# reader.net
KiCad netlist of a schematic drawn in EAGLE
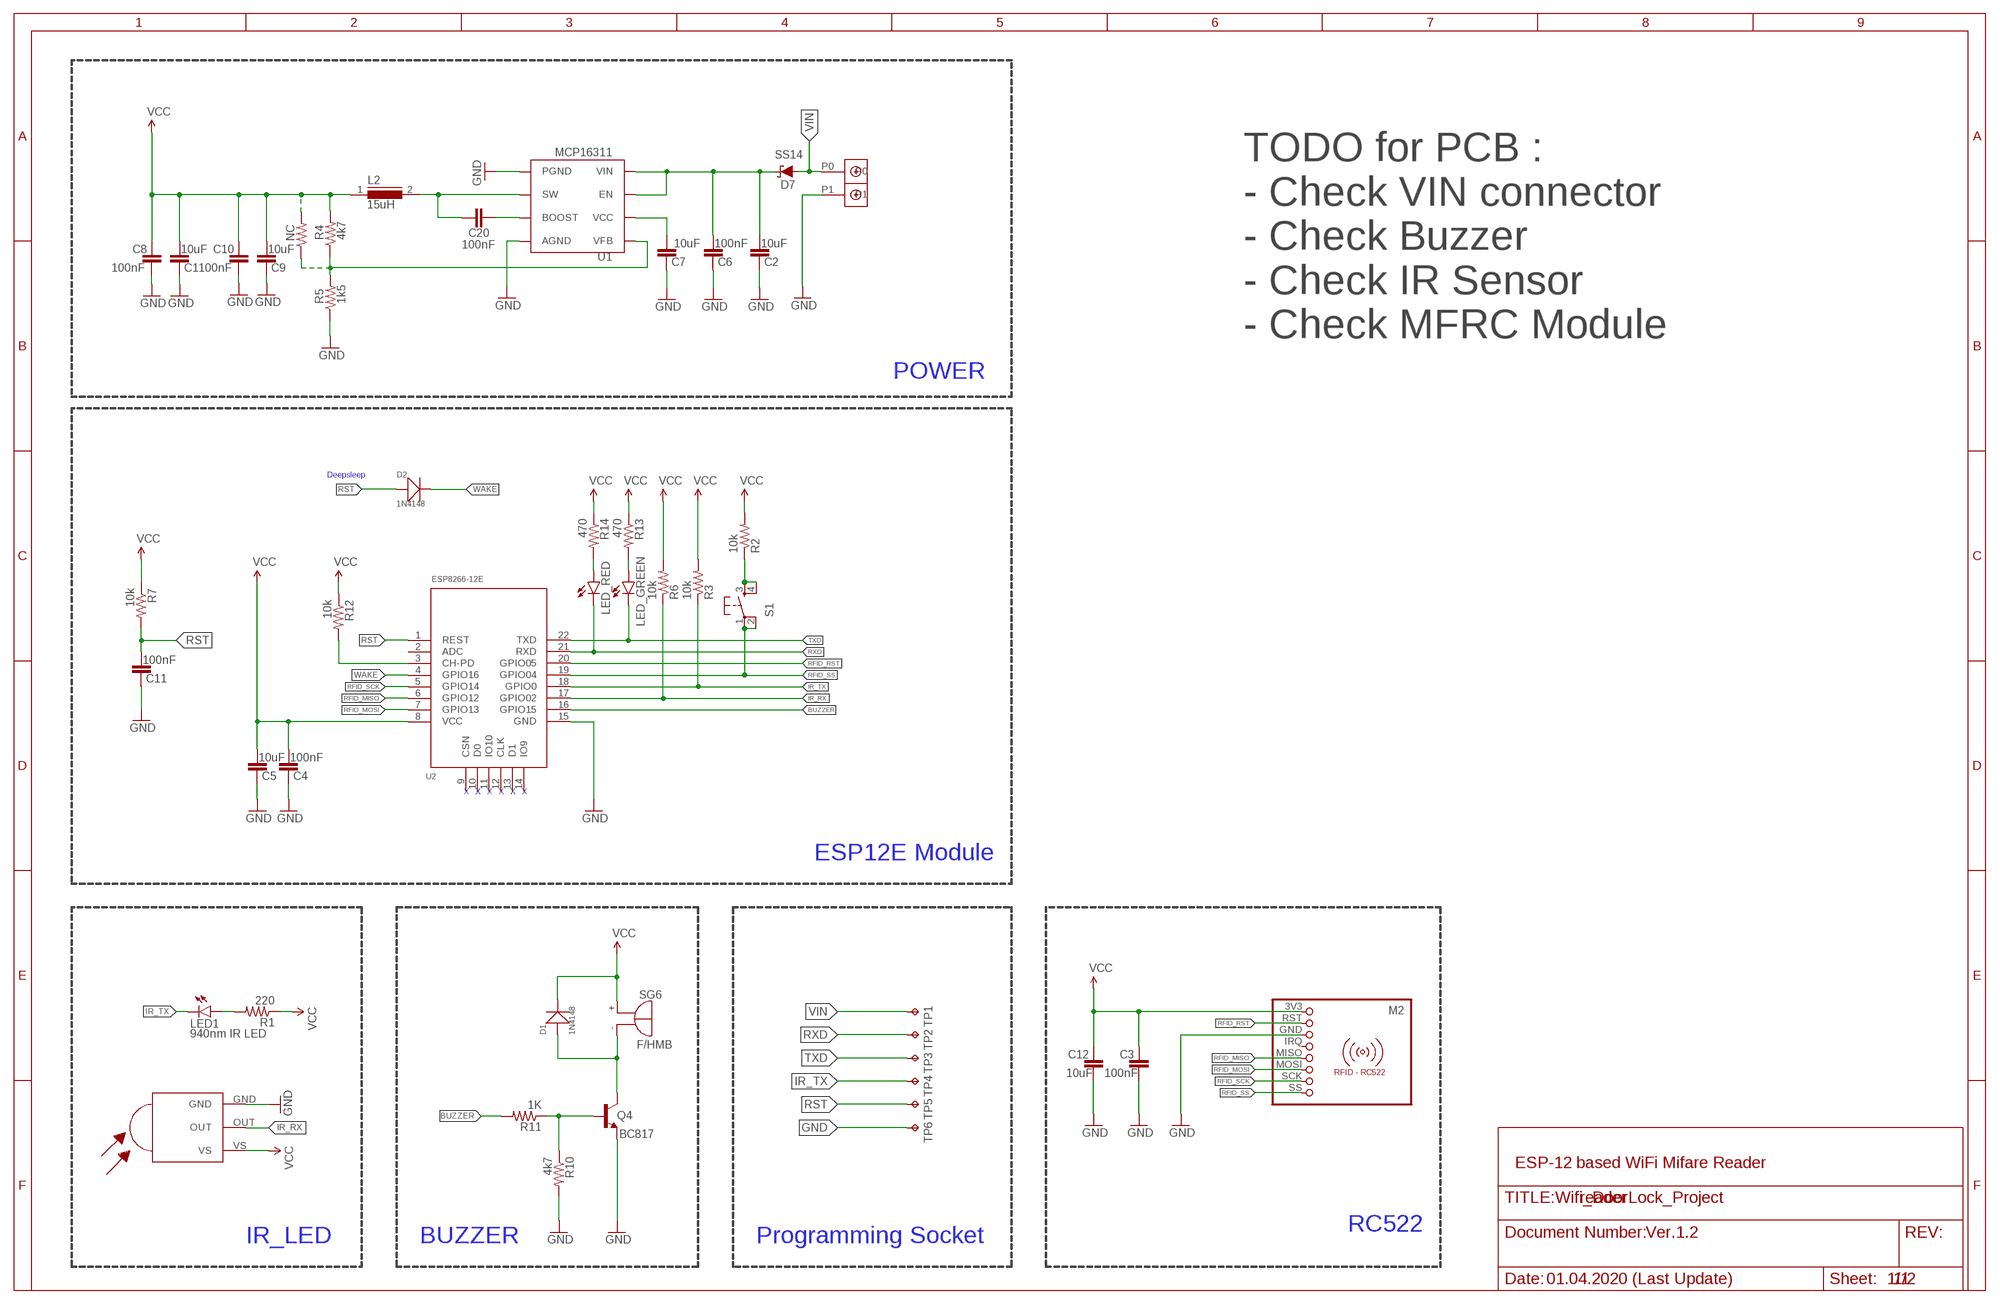
[diagram p0: schematic, sheet 1]

(export (version "E")
  (design (tool "Eeschema 10.0.6"))
  (components
    (comp (ref "C1")
      (value "10uF")
      (footprint "eagle-import:C0805")
      (libsource (lib "eagle-import") (part "C-EUC0805"))
    )
    (comp (ref "C2")
      (value "10uF")
      (footprint "eagle-import:C0805")
      (libsource (lib "eagle-import") (part "C-EUC0805"))
    )
    (comp (ref "C3")
      (value "100nF")
      (footprint "eagle-import:C0805")
      (libsource (lib "eagle-import") (part "C-EUC0805"))
    )
    (comp (ref "C4")
      (value "100nF")
      (footprint "eagle-import:C0805")
      (libsource (lib "eagle-import") (part "C-EUC0805"))
    )
    (comp (ref "C5")
      (value "10uF")
      (footprint "eagle-import:C0805")
      (libsource (lib "eagle-import") (part "C-EUC0805"))
    )
    (comp (ref "C6")
      (value "100nF")
      (footprint "eagle-import:C0805")
      (libsource (lib "eagle-import") (part "C-EUC0805"))
    )
    (comp (ref "C7")
      (value "10uF")
      (footprint "eagle-import:C0805")
      (libsource (lib "eagle-import") (part "C-EUC0805"))
    )
    (comp (ref "C8")
      (value "100nF")
      (footprint "eagle-import:C0805")
      (libsource (lib "eagle-import") (part "C-EUC0805"))
    )
    (comp (ref "C9")
      (value "10uF")
      (footprint "eagle-import:C0805")
      (libsource (lib "eagle-import") (part "C-EUC0805"))
    )
    (comp (ref "C10")
      (value "100nF")
      (footprint "eagle-import:C0805")
      (libsource (lib "eagle-import") (part "C-EUC0805"))
    )
    (comp (ref "C11")
      (value "100nF")
      (footprint "eagle-import:C0805")
      (libsource (lib "eagle-import") (part "C-EUC0805"))
    )
    (comp (ref "C12")
      (value "10uF")
      (footprint "eagle-import:C0805")
      (libsource (lib "eagle-import") (part "C-EUC0805"))
    )
    (comp (ref "C20")
      (value "100nF")
      (footprint "eagle-import:C0805")
      (libsource (lib "eagle-import") (part "C-EUC0805"))
    )
    (comp (ref "D1")
      (value "1N4148")
      (footprint "eagle-import:LL-34")
      (libsource (lib "eagle-import") (part "SMD-DIODE-SWITCH-1N4148(LL-34)"))
    )
    (comp (ref "D2")
      (value "1N4148")
      (footprint "eagle-import:LL-34")
      (libsource (lib "eagle-import") (part "SMD-DIODE-SWITCH-1N4148(LL-34)"))
    )
    (comp (ref "D7")
      (value "SS14")
      (footprint "eagle-import:SMA-DIODE")
      (libsource (lib "eagle-import") (part "DIODE-SCHOTTKY-SS14"))
    )
    (comp (ref "L2")
      (value "15uH")
      (footprint "eagle-import:DR74")
      (libsource (lib "eagle-import") (part "DR74"))
    )
    (comp (ref "LED1")
      (value "940nm IR LED")
      (footprint "eagle-import:LED3MM")
      (libsource (lib "eagle-import") (part "LED3MM"))
    )
    (comp (ref "LED_GREEN")
      (value "LED3MM")
      (footprint "eagle-import:LED3MM")
      (libsource (lib "eagle-import") (part "LED3MM"))
    )
    (comp (ref "LED_RED")
      (value "LED3MM")
      (footprint "eagle-import:LED3MM")
      (libsource (lib "eagle-import") (part "LED3MM"))
    )
    (comp (ref "M2")
      (value "RFID-RC522")
      (footprint "eagle-import:RFID-RC522")
      (libsource (lib "eagle-import") (part "RFID-RC522"))
    )
    (comp (ref "NC")
      (value "R-US_M0805")
      (footprint "eagle-import:M0805")
      (libsource (lib "eagle-import") (part "R-US_M0805"))
    )
    (comp (ref "Q4")
      (value "BC817")
      (footprint "eagle-import:SOT-23")
      (libsource (lib "eagle-import") (part "TRANSISTOR_BJT_NPN-SOT-23-BCE"))
    )
    (comp (ref "R1")
      (value "220")
      (footprint "eagle-import:M0805")
      (libsource (lib "eagle-import") (part "R-US_M0805"))
    )
    (comp (ref "R2")
      (value "10k")
      (footprint "eagle-import:M0805")
      (libsource (lib "eagle-import") (part "R-US_M0805"))
    )
    (comp (ref "R3")
      (value "10k")
      (footprint "eagle-import:M0805")
      (libsource (lib "eagle-import") (part "R-US_M0805"))
    )
    (comp (ref "R4")
      (value "4k7")
      (footprint "eagle-import:M0805")
      (libsource (lib "eagle-import") (part "R-US_M0805"))
    )
    (comp (ref "R5")
      (value "1k5")
      (footprint "eagle-import:M0805")
      (libsource (lib "eagle-import") (part "R-US_M0805"))
    )
    (comp (ref "R6")
      (value "10k")
      (footprint "eagle-import:M0805")
      (libsource (lib "eagle-import") (part "R-US_M0805"))
    )
    (comp (ref "R7")
      (value "10k")
      (footprint "eagle-import:M0805")
      (libsource (lib "eagle-import") (part "R-US_M0805"))
    )
    (comp (ref "R10")
      (value "4k7")
      (footprint "eagle-import:M0805")
      (libsource (lib "eagle-import") (part "R-US_M0805"))
    )
    (comp (ref "R11")
      (value "1K")
      (footprint "eagle-import:M0805")
      (libsource (lib "eagle-import") (part "R-US_M0805"))
    )
    (comp (ref "R12")
      (value "10k")
      (footprint "eagle-import:M0805")
      (libsource (lib "eagle-import") (part "R-US_M0805"))
    )
    (comp (ref "R13")
      (value "470")
      (footprint "eagle-import:M0805")
      (libsource (lib "eagle-import") (part "R-US_M0805"))
    )
    (comp (ref "R14")
      (value "470")
      (footprint "eagle-import:M0805")
      (libsource (lib "eagle-import") (part "R-US_M0805"))
    )
    (comp (ref "S1")
      (value "FLASH")
      (footprint "eagle-import:TACTILE-PTH")
      (libsource (lib "eagle-import") (part "TAC_SWITCHPTH"))
    )
    (comp (ref "SG6")
      (value "F/HMB")
      (footprint "eagle-import:F_HMB")
      (libsource (lib "eagle-import") (part "F/HMB"))
    )
    (comp (ref "TP1")
      (value "TPTP20SQ")
      (footprint "eagle-import:TP20SQ")
      (libsource (lib "eagle-import") (part "TPTP20SQ"))
    )
    (comp (ref "TP2")
      (value "TPTP20SQ")
      (footprint "eagle-import:TP20SQ")
      (libsource (lib "eagle-import") (part "TPTP20SQ"))
    )
    (comp (ref "TP3")
      (value "TPTP20SQ")
      (footprint "eagle-import:TP20SQ")
      (libsource (lib "eagle-import") (part "TPTP20SQ"))
    )
    (comp (ref "TP4")
      (value "TPTP20SQ")
      (footprint "eagle-import:TP20SQ")
      (libsource (lib "eagle-import") (part "TPTP20SQ"))
    )
    (comp (ref "TP5")
      (value "TPTP20SQ")
      (footprint "eagle-import:TP20SQ")
      (libsource (lib "eagle-import") (part "TPTP20SQ"))
    )
    (comp (ref "TP6")
      (value "TPTP20SQ")
      (footprint "eagle-import:TP20SQ")
      (libsource (lib "eagle-import") (part "TPTP20SQ"))
    )
    (comp (ref "U$1")
      (value "DBCONN-1X2")
      (footprint "eagle-import:DBCONN-1X2")
      (libsource (lib "eagle-import") (part "DBCONN-1X2"))
    )
    (comp (ref "U$3")
      (value "TSOP18")
      (footprint "eagle-import:TSOP-382")
      (fields
        (field (name "DIGI-KEY_PART_NUMBER") "751-1227-ND")
        (field (name "MF") "Vishay")
        (field (name "MP") "TSOP38238")
      )
      (libsource (lib "eagle-import") (part "TSOP38238"))
    )
    (comp (ref "U1")
      (value "MCP16311")
      (footprint "eagle-import:MSOP8")
      (libsource (lib "eagle-import") (part "MCP16311"))
    )
    (comp (ref "U2")
      (value "ESP8266-12E")
      (footprint "eagle-import:LGA22-2.0-24X16MM")
      (fields (field (name "MPN") "ESP8266-12E/ESP-12E"))
      (libsource (lib "eagle-import") (part "MOUDLE-WIFI-ESP8266-12E/ESP-12E(22P-24X16MM)"))
    )
  )
  (nets
    (net (code "1") (name "BUZZER") (class "Default")
      (node (ref "R11") (pin "2") (pinfunction "2_2") (pintype "passive"))
      (node (ref "U2") (pin "16") (pinfunction "GPIO15_16") (pintype "bidirectional"))
    )
    (net (code "2") (name "GND") (class "Default")
      (node (ref "C1") (pin "1") (pinfunction "1_1") (pintype "passive"))
      (node (ref "C10") (pin "2") (pinfunction "2_2") (pintype "passive"))
      (node (ref "C11") (pin "1") (pinfunction "1_1") (pintype "passive"))
      (node (ref "C12") (pin "2") (pinfunction "2_2") (pintype "passive"))
      (node (ref "C2") (pin "1") (pinfunction "1_1") (pintype "passive"))
      (node (ref "C3") (pin "2") (pinfunction "2_2") (pintype "passive"))
      (node (ref "C4") (pin "1") (pinfunction "1_1") (pintype "passive"))
      (node (ref "C5") (pin "1") (pinfunction "1_1") (pintype "passive"))
      (node (ref "C6") (pin "1") (pinfunction "1_1") (pintype "passive"))
      (node (ref "C7") (pin "1") (pinfunction "1_1") (pintype "passive"))
      (node (ref "C8") (pin "2") (pinfunction "2_2") (pintype "passive"))
      (node (ref "C9") (pin "1") (pinfunction "1_1") (pintype "passive"))
      (node (ref "M2") (pin "GND") (pinfunction "3_GND") (pintype "passive"))
      (node (ref "Q4") (pin "3") (pinfunction "E_3") (pintype "passive"))
      (node (ref "R10") (pin "2") (pinfunction "2_2") (pintype "passive"))
      (node (ref "R5") (pin "1") (pinfunction "1_1") (pintype "passive"))
      (node (ref "TP6") (pin "TP") (pinfunction "TP_TP") (pintype "input"))
      (node (ref "U$1") (pin "P1") (pinfunction "P1_P1") (pintype "bidirectional"))
      (node (ref "U$3") (pin "GND") (pinfunction "GND_GND") (pintype "bidirectional"))
      (node (ref "U1") (pin "AGND") (pinfunction "AGND_AGND") (pintype "bidirectional"))
      (node (ref "U1") (pin "PGND") (pinfunction "PGND_PGND") (pintype "bidirectional"))
      (node (ref "U2") (pin "15") (pinfunction "GND_15") (pintype "bidirectional"))
    )
    (net (code "3") (name "IR_RX") (class "Default")
      (node (ref "R6") (pin "1") (pinfunction "1_1") (pintype "passive"))
      (node (ref "U$3") (pin "OUT") (pinfunction "OUT_OUT") (pintype "bidirectional"))
      (node (ref "U2") (pin "17") (pinfunction "GPIO02_17") (pintype "bidirectional"))
    )
    (net (code "4") (name "IR_TX") (class "Default")
      (node (ref "LED1") (pin "K") (pinfunction "C_K") (pintype "passive"))
      (node (ref "R3") (pin "1") (pinfunction "1_1") (pintype "passive"))
      (node (ref "TP4") (pin "TP") (pinfunction "TP_TP") (pintype "input"))
      (node (ref "U2") (pin "18") (pinfunction "GPIO0_18") (pintype "bidirectional"))
    )
    (net (code "5") (name "Net-(C2-Pad2)") (class "Default")
      (node (ref "C2") (pin "2") (pinfunction "2_2") (pintype "passive"))
      (node (ref "C6") (pin "2") (pinfunction "2_2") (pintype "passive"))
      (node (ref "D7") (pin "C") (pinfunction "C_C") (pintype "passive"))
      (node (ref "U1") (pin "EN") (pinfunction "EN_EN") (pintype "bidirectional"))
      (node (ref "U1") (pin "VIN") (pinfunction "VIN_VIN") (pintype "bidirectional"))
    )
    (net (code "6") (name "Net-(C7-Pad2)") (class "Default")
      (node (ref "C7") (pin "2") (pinfunction "2_2") (pintype "passive"))
      (node (ref "U1") (pin "VCC") (pinfunction "VCC_VCC") (pintype "bidirectional"))
    )
    (net (code "7") (name "Net-(C20-Pad1)") (class "Default")
      (node (ref "C20") (pin "1") (pinfunction "1_1") (pintype "passive"))
      (node (ref "U1") (pin "BOOST") (pinfunction "BOOST_BOOST") (pintype "bidirectional"))
    )
    (net (code "8") (name "Net-(C20-Pad2)") (class "Default")
      (node (ref "C20") (pin "2") (pinfunction "2_2") (pintype "passive"))
      (node (ref "L2") (pin "2") (pinfunction "2_2") (pintype "passive"))
      (node (ref "U1") (pin "SW") (pinfunction "SW_SW") (pintype "bidirectional"))
    )
    (net (code "9") (name "Net-(D1-+)") (class "Default")
      (node (ref "D1") (pin "A") (pinfunction "+_A") (pintype "passive"))
      (node (ref "Q4") (pin "2") (pinfunction "C_2") (pintype "passive"))
      (node (ref "SG6") (pin "-") (pinfunction "-_-") (pintype "passive"))
    )
    (net (code "10") (name "Net-(LED1-PadA)") (class "Default")
      (node (ref "LED1") (pin "A") (pinfunction "A_A") (pintype "passive"))
      (node (ref "R1") (pin "2") (pinfunction "2_2") (pintype "passive"))
    )
    (net (code "11") (name "Net-(LED_GREEN-PadA)") (class "Default")
      (node (ref "LED_GREEN") (pin "A") (pinfunction "A_A") (pintype "passive"))
      (node (ref "R13") (pin "2") (pinfunction "2_2") (pintype "passive"))
    )
    (net (code "12") (name "Net-(LED_RED-PadA)") (class "Default")
      (node (ref "LED_RED") (pin "A") (pinfunction "A_A") (pintype "passive"))
      (node (ref "R14") (pin "2") (pinfunction "2_2") (pintype "passive"))
    )
    (net (code "13") (name "Net-(NC-Pad1)") (class "Default")
      (node (ref "NC") (pin "1") (pinfunction "1_1") (pintype "passive"))
      (node (ref "R4") (pin "1") (pinfunction "1_1") (pintype "passive"))
      (node (ref "R5") (pin "2") (pinfunction "2_2") (pintype "passive"))
      (node (ref "U1") (pin "VFB") (pinfunction "VFB_VFB") (pintype "bidirectional"))
    )
    (net (code "14") (name "Net-(Q4-B)") (class "Default")
      (node (ref "Q4") (pin "1") (pinfunction "B_1") (pintype "passive"))
      (node (ref "R10") (pin "1") (pinfunction "1_1") (pintype "passive"))
      (node (ref "R11") (pin "1") (pinfunction "1_1") (pintype "passive"))
    )
    (net (code "15") (name "Net-(R2-Pad1)") (class "Default")
      (node (ref "R2") (pin "1") (pinfunction "1_1") (pintype "passive"))
      (node (ref "S1") (pin "3") (pinfunction "3_3") (pintype "passive"))
      (node (ref "S1") (pin "4") (pinfunction "4_4") (pintype "passive"))
    )
    (net (code "16") (name "Net-(U2-CH-PD)") (class "Default")
      (node (ref "R12") (pin "2") (pinfunction "2_2") (pintype "passive"))
      (node (ref "U2") (pin "3") (pinfunction "CH-PD_3") (pintype "bidirectional"))
    )
    (net (code "17") (name "RFID_MISO") (class "Default")
      (node (ref "M2") (pin "MISO") (pinfunction "5_MISO") (pintype "passive"))
      (node (ref "U2") (pin "6") (pinfunction "GPIO12_6") (pintype "bidirectional"))
    )
    (net (code "18") (name "RFID_MOSI") (class "Default")
      (node (ref "M2") (pin "MOSI") (pinfunction "6_MOSI") (pintype "passive"))
      (node (ref "U2") (pin "7") (pinfunction "GPIO13_7") (pintype "bidirectional"))
    )
    (net (code "19") (name "RFID_RST") (class "Default")
      (node (ref "M2") (pin "RST") (pinfunction "2_RST") (pintype "passive"))
      (node (ref "U2") (pin "20") (pinfunction "GPIO05_20") (pintype "bidirectional"))
    )
    (net (code "20") (name "RFID_SCK") (class "Default")
      (node (ref "M2") (pin "SCK") (pinfunction "7_SCK") (pintype "passive"))
      (node (ref "U2") (pin "5") (pinfunction "GPIO14_5") (pintype "bidirectional"))
    )
    (net (code "21") (name "RFID_SS") (class "Default")
      (node (ref "M2") (pin "SS") (pinfunction "8_SS") (pintype "passive"))
      (node (ref "S1") (pin "1") (pinfunction "1_1") (pintype "passive"))
      (node (ref "S1") (pin "2") (pinfunction "2_2") (pintype "passive"))
      (node (ref "U2") (pin "19") (pinfunction "GPIO04_19") (pintype "bidirectional"))
    )
    (net (code "22") (name "RST") (class "Default")
      (node (ref "C11") (pin "2") (pinfunction "2_2") (pintype "passive"))
      (node (ref "D2") (pin "A") (pinfunction "+_A") (pintype "passive"))
      (node (ref "R7") (pin "2") (pinfunction "2_2") (pintype "passive"))
      (node (ref "TP5") (pin "TP") (pinfunction "TP_TP") (pintype "input"))
      (node (ref "U2") (pin "1") (pinfunction "REST_1") (pintype "bidirectional"))
    )
    (net (code "23") (name "RXD") (class "Default")
      (node (ref "LED_RED") (pin "K") (pinfunction "C_K") (pintype "passive"))
      (node (ref "TP2") (pin "TP") (pinfunction "TP_TP") (pintype "input"))
      (node (ref "U2") (pin "21") (pinfunction "RXD_21") (pintype "bidirectional"))
    )
    (net (code "24") (name "TXD") (class "Default")
      (node (ref "LED_GREEN") (pin "K") (pinfunction "C_K") (pintype "passive"))
      (node (ref "TP3") (pin "TP") (pinfunction "TP_TP") (pintype "input"))
      (node (ref "U2") (pin "22") (pinfunction "TXD_22") (pintype "bidirectional"))
    )
    (net (code "25") (name "VCC") (class "Default")
      (node (ref "C1") (pin "2") (pinfunction "2_2") (pintype "passive"))
      (node (ref "C10") (pin "1") (pinfunction "1_1") (pintype "passive"))
      (node (ref "C12") (pin "1") (pinfunction "1_1") (pintype "passive"))
      (node (ref "C3") (pin "1") (pinfunction "1_1") (pintype "passive"))
      (node (ref "C4") (pin "2") (pinfunction "2_2") (pintype "passive"))
      (node (ref "C5") (pin "2") (pinfunction "2_2") (pintype "passive"))
      (node (ref "C8") (pin "1") (pinfunction "1_1") (pintype "passive"))
      (node (ref "C9") (pin "2") (pinfunction "2_2") (pintype "passive"))
      (node (ref "D1") (pin "C") (pinfunction "-_C") (pintype "passive"))
      (node (ref "L2") (pin "1") (pinfunction "1_1") (pintype "passive"))
      (node (ref "M2") (pin "3V3") (pinfunction "1_3V3") (pintype "passive"))
      (node (ref "NC") (pin "2") (pinfunction "2_2") (pintype "passive"))
      (node (ref "R1") (pin "1") (pinfunction "1_1") (pintype "passive"))
      (node (ref "R12") (pin "1") (pinfunction "1_1") (pintype "passive"))
      (node (ref "R13") (pin "1") (pinfunction "1_1") (pintype "passive"))
      (node (ref "R14") (pin "1") (pinfunction "1_1") (pintype "passive"))
      (node (ref "R2") (pin "2") (pinfunction "2_2") (pintype "passive"))
      (node (ref "R3") (pin "2") (pinfunction "2_2") (pintype "passive"))
      (node (ref "R4") (pin "2") (pinfunction "2_2") (pintype "passive"))
      (node (ref "R6") (pin "2") (pinfunction "2_2") (pintype "passive"))
      (node (ref "R7") (pin "1") (pinfunction "1_1") (pintype "passive"))
      (node (ref "SG6") (pin "+") (pinfunction "+_+") (pintype "passive"))
      (node (ref "U$3") (pin "VS") (pinfunction "VS_VS") (pintype "bidirectional"))
      (node (ref "U2") (pin "8") (pinfunction "VCC_8") (pintype "bidirectional"))
    )
    (net (code "26") (name "VIN") (class "Default")
      (node (ref "D7") (pin "A") (pinfunction "A_A") (pintype "passive"))
      (node (ref "TP1") (pin "TP") (pinfunction "TP_TP") (pintype "input"))
      (node (ref "U$1") (pin "P0") (pinfunction "P0_P0") (pintype "bidirectional"))
    )
    (net (code "27") (name "WAKE") (class "Default")
      (node (ref "D2") (pin "C") (pinfunction "-_C") (pintype "passive"))
      (node (ref "U2") (pin "4") (pinfunction "GPIO16_4") (pintype "bidirectional"))
    )
    (net (code "28") (name "unconnected-(M2-4-PadIRQ)") (class "Default")
      (node (ref "M2") (pin "IRQ") (pinfunction "4_IRQ") (pintype "passive"))
    )
    (net (code "29") (name "unconnected-(U2-ADC-Pad2)") (class "Default")
      (node (ref "U2") (pin "2") (pinfunction "ADC_2") (pintype "bidirectional"))
    )
    (net (code "30") (name "unconnected-(U2-CLK-Pad12)") (class "Default")
      (node (ref "U2") (pin "12") (pinfunction "CLK_12") (pintype "bidirectional"))
    )
    (net (code "31") (name "unconnected-(U2-CSN-Pad9)") (class "Default")
      (node (ref "U2") (pin "9") (pinfunction "CSN_9") (pintype "bidirectional"))
    )
    (net (code "32") (name "unconnected-(U2-D0-Pad10)") (class "Default")
      (node (ref "U2") (pin "10") (pinfunction "D0_10") (pintype "bidirectional"))
    )
    (net (code "33") (name "unconnected-(U2-D1-Pad13)") (class "Default")
      (node (ref "U2") (pin "13") (pinfunction "D1_13") (pintype "bidirectional"))
    )
    (net (code "34") (name "unconnected-(U2-IO9-Pad14)") (class "Default")
      (node (ref "U2") (pin "14") (pinfunction "IO9_14") (pintype "bidirectional"))
    )
    (net (code "35") (name "unconnected-(U2-IO10-Pad11)") (class "Default")
      (node (ref "U2") (pin "11") (pinfunction "IO10_11") (pintype "bidirectional"))
    )
  )
)
